# remotoPro1_3.net
KiCad netlist of a schematic drawn in EAGLE
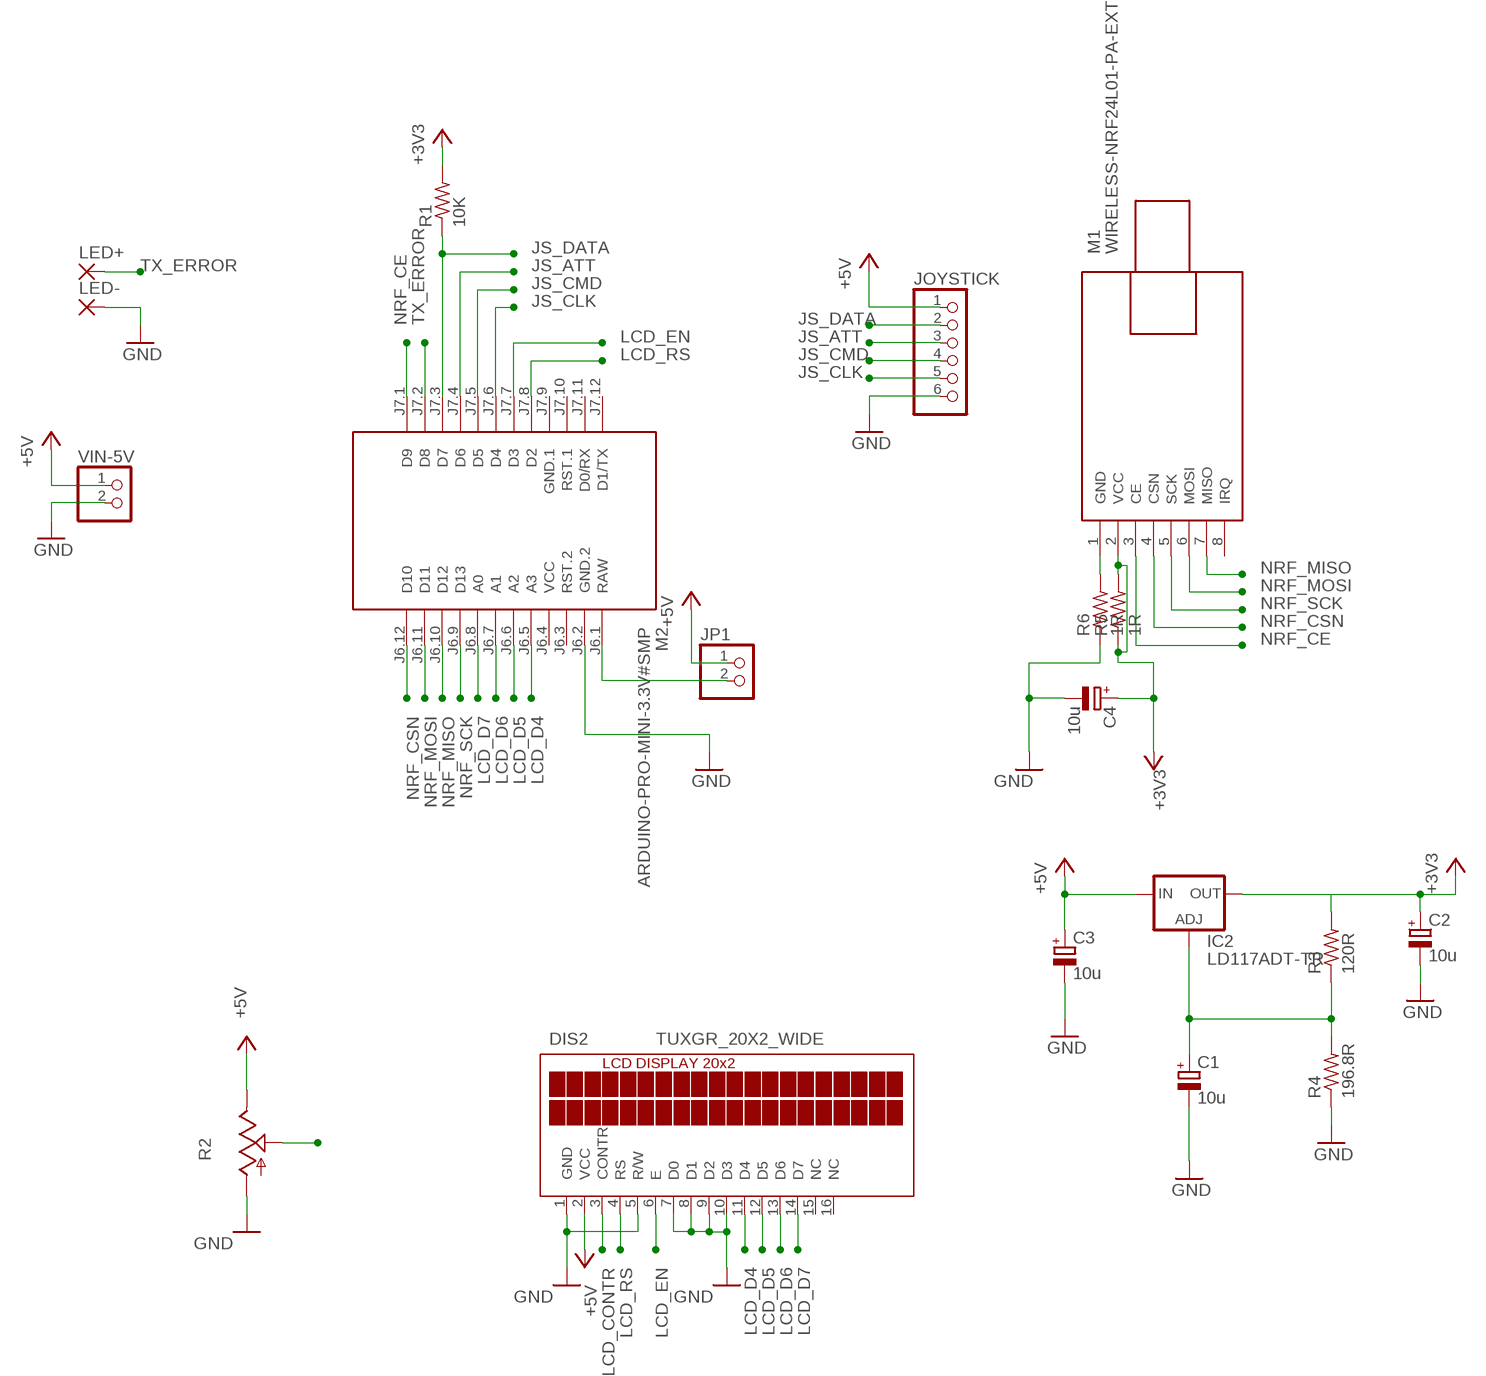
[diagram p0: schematic, sheet 1]

(export (version "E")
  (design (tool "Eeschema 10.0.6"))
  (components
    (comp (ref "C1")
      (value "10u")
      (footprint "eagle-import:E1,8-4")
      (libsource (lib "eagle-import") (part "CPOL-EUE1.8-4"))
    )
    (comp (ref "C2")
      (value "10u")
      (footprint "eagle-import:E1,8-4")
      (libsource (lib "eagle-import") (part "CPOL-EUE1.8-4"))
    )
    (comp (ref "C3")
      (value "10u")
      (footprint "eagle-import:E1,8-4")
      (libsource (lib "eagle-import") (part "CPOL-EUE1.8-4"))
    )
    (comp (ref "C4")
      (value "10u")
      (footprint "eagle-import:E1,8-4")
      (libsource (lib "eagle-import") (part "CPOL-EUE1.8-4"))
    )
    (comp (ref "DIS2")
      (value "TUXGR_20X2_WIDE")
      (footprint "eagle-import:TUXGR_20X2_WIDE")
      (libsource (lib "eagle-import") (part "TUXGR_20X2_WIDE"))
    )
    (comp (ref "IC2")
      (value "LD117ADT-TR")
      (footprint "eagle-import:DPACK")
      (libsource (lib "eagle-import") (part "LD117A?DT-TR"))
    )
    (comp (ref "JOYSTICK")
      (value "PINHD-1X6")
      (footprint "eagle-import:1X06")
      (libsource (lib "eagle-import") (part "PINHD-1X6"))
    )
    (comp (ref "JP1")
      (value "PINHD-1X2")
      (footprint "eagle-import:1X02")
      (libsource (lib "eagle-import") (part "PINHD-1X2"))
    )
    (comp (ref "LED+")
      (value "1,6/0,8")
      (footprint "eagle-import:1,6_0,8")
      (libsource (lib "eagle-import") (part "1,6/0,8"))
    )
    (comp (ref "LED-")
      (value "1,6/0,8")
      (footprint "eagle-import:1,6_0,8")
      (libsource (lib "eagle-import") (part "1,6/0,8"))
    )
    (comp (ref "M1")
      (value "WIRELESS-NRF24L01-PA-EXT")
      (footprint "eagle-import:WIRELESS-NRF24L01-PA-EXT")
      (libsource (lib "eagle-import") (part "WIRELESS-NRF24L01-PA-EXT"))
    )
    (comp (ref "M2")
      (value "ARDUINO-PRO-MINI-3.3V#SMP")
      (footprint "eagle-import:ARDUINO-PRO-MINI#SMP")
      (libsource (lib "eagle-import") (part "ARDUINO-PRO-MINI-#SMP3.3V"))
    )
    (comp (ref "R1")
      (value "10K")
      (footprint "eagle-import:0204_7")
      (libsource (lib "eagle-import") (part "R-US_0204/7"))
    )
    (comp (ref "R2")
      (value "TRIM_US-S75P")
      (footprint "eagle-import:S75P")
      (libsource (lib "eagle-import") (part "TRIM_US-S75P"))
    )
    (comp (ref "R3")
      (value "120R")
      (footprint "eagle-import:0204_7")
      (libsource (lib "eagle-import") (part "R-US_0204/7"))
    )
    (comp (ref "R4")
      (value "196.8R")
      (footprint "eagle-import:0204_7")
      (libsource (lib "eagle-import") (part "R-US_0204/7"))
    )
    (comp (ref "R5")
      (value "1R")
      (footprint "eagle-import:0207_2V")
      (libsource (lib "eagle-import") (part "R-US_0207/2V"))
    )
    (comp (ref "R6")
      (value "1R")
      (footprint "eagle-import:0207_2V")
      (libsource (lib "eagle-import") (part "R-US_0207/2V"))
    )
    (comp (ref "VIN-5V")
      (value "PINHD-1X2")
      (footprint "eagle-import:1X02")
      (libsource (lib "eagle-import") (part "PINHD-1X2"))
    )
  )
  (nets
    (net (code "1") (name "+3V3") (class "Default")
      (node (ref "C2") (pin "+") (pinfunction "+_+") (pintype "passive"))
      (node (ref "C4") (pin "+") (pinfunction "+_+") (pintype "passive"))
      (node (ref "IC2") (pin "4") (pinfunction "OUT_4") (pintype "passive"))
      (node (ref "M1") (pin "2") (pinfunction "VCC_2") (pintype "power_in"))
      (node (ref "R1") (pin "2") (pinfunction "2_2") (pintype "passive"))
      (node (ref "R3") (pin "2") (pinfunction "2_2") (pintype "passive"))
      (node (ref "R5") (pin "1") (pinfunction "1_1") (pintype "passive"))
      (node (ref "R5") (pin "2") (pinfunction "2_2") (pintype "passive"))
    )
    (net (code "2") (name "+5V") (class "Default")
      (node (ref "C3") (pin "+") (pinfunction "+_+") (pintype "passive"))
      (node (ref "DIS2") (pin "2") (pinfunction "VCC_2") (pintype "power_in"))
      (node (ref "IC2") (pin "3") (pinfunction "IN_3") (pintype "input"))
      (node (ref "JOYSTICK") (pin "1") (pinfunction "1_1") (pintype "passive"))
      (node (ref "JP1") (pin "1") (pinfunction "1_1") (pintype "passive"))
      (node (ref "R2") (pin "E") (pinfunction "E_E") (pintype "passive"))
      (node (ref "VIN-5V") (pin "1") (pinfunction "1_1") (pintype "passive"))
    )
    (net (code "3") (name "/GND.1") (class "Default")
      (node (ref "M2") (pin "J7.9") (pinfunction "GND.1_J7.9") (pintype "power_in"))
    )
    (net (code "4") (name "/JS_ATT") (class "Default")
      (node (ref "JOYSTICK") (pin "3") (pinfunction "3_3") (pintype "passive"))
      (node (ref "M2") (pin "J7.4") (pinfunction "D6_J7.4") (pintype "bidirectional"))
    )
    (net (code "5") (name "/JS_CLK") (class "Default")
      (node (ref "JOYSTICK") (pin "5") (pinfunction "5_5") (pintype "passive"))
      (node (ref "M2") (pin "J7.6") (pinfunction "D4_J7.6") (pintype "bidirectional"))
    )
    (net (code "6") (name "/JS_CMD") (class "Default")
      (node (ref "JOYSTICK") (pin "4") (pinfunction "4_4") (pintype "passive"))
      (node (ref "M2") (pin "J7.5") (pinfunction "D5_J7.5") (pintype "bidirectional"))
    )
    (net (code "7") (name "/JS_DATA") (class "Default")
      (node (ref "JOYSTICK") (pin "2") (pinfunction "2_2") (pintype "passive"))
      (node (ref "M2") (pin "J7.3") (pinfunction "D7_J7.3") (pintype "bidirectional"))
      (node (ref "R1") (pin "1") (pinfunction "1_1") (pintype "passive"))
    )
    (net (code "8") (name "/LCD_CONTR") (class "Default")
      (node (ref "DIS2") (pin "3") (pinfunction "CONTR_3") (pintype "input"))
      (node (ref "R2") (pin "S") (pinfunction "S_S") (pintype "passive"))
    )
    (net (code "9") (name "/LCD_D4") (class "Default")
      (node (ref "DIS2") (pin "11") (pinfunction "D4_11") (pintype "input"))
      (node (ref "M2") (pin "J6.5") (pinfunction "A3_J6.5") (pintype "bidirectional"))
    )
    (net (code "10") (name "/LCD_D5") (class "Default")
      (node (ref "DIS2") (pin "12") (pinfunction "D5_12") (pintype "input"))
      (node (ref "M2") (pin "J6.6") (pinfunction "A2_J6.6") (pintype "bidirectional"))
    )
    (net (code "11") (name "/LCD_D6") (class "Default")
      (node (ref "DIS2") (pin "13") (pinfunction "D6_13") (pintype "input"))
      (node (ref "M2") (pin "J6.7") (pinfunction "A1_J6.7") (pintype "bidirectional"))
    )
    (net (code "12") (name "/LCD_D7") (class "Default")
      (node (ref "DIS2") (pin "14") (pinfunction "D7_14") (pintype "input"))
      (node (ref "M2") (pin "J6.8") (pinfunction "A0_J6.8") (pintype "bidirectional"))
    )
    (net (code "13") (name "/LCD_EN") (class "Default")
      (node (ref "DIS2") (pin "6") (pinfunction "E_6") (pintype "input"))
      (node (ref "M2") (pin "J7.7") (pinfunction "D3_J7.7") (pintype "bidirectional"))
    )
    (net (code "14") (name "/LCD_RS") (class "Default")
      (node (ref "DIS2") (pin "4") (pinfunction "RS_4") (pintype "input"))
      (node (ref "M2") (pin "J7.8") (pinfunction "D2_J7.8") (pintype "bidirectional"))
    )
    (net (code "15") (name "/NRF_CE") (class "Default")
      (node (ref "M1") (pin "3") (pinfunction "CE_3") (pintype "bidirectional"))
      (node (ref "M2") (pin "J7.1") (pinfunction "D9_J7.1") (pintype "bidirectional"))
    )
    (net (code "16") (name "/NRF_CSN") (class "Default")
      (node (ref "M1") (pin "4") (pinfunction "CSN_4") (pintype "bidirectional"))
      (node (ref "M2") (pin "J6.12") (pinfunction "D10_J6.12") (pintype "bidirectional"))
    )
    (net (code "17") (name "/NRF_MISO") (class "Default")
      (node (ref "M1") (pin "7") (pinfunction "MISO_7") (pintype "bidirectional"))
      (node (ref "M2") (pin "J6.10") (pinfunction "D12_J6.10") (pintype "bidirectional"))
    )
    (net (code "18") (name "/NRF_MOSI") (class "Default")
      (node (ref "M1") (pin "6") (pinfunction "MOSI_6") (pintype "bidirectional"))
      (node (ref "M2") (pin "J6.11") (pinfunction "D11_J6.11") (pintype "bidirectional"))
    )
    (net (code "19") (name "/NRF_SCK") (class "Default")
      (node (ref "M1") (pin "5") (pinfunction "SCK_5") (pintype "bidirectional"))
      (node (ref "M2") (pin "J6.9") (pinfunction "D13_J6.9") (pintype "bidirectional"))
    )
    (net (code "20") (name "/TX_ERROR") (class "Default")
      (node (ref "LED+") (pin "1") (pinfunction "P_1") (pintype "passive"))
      (node (ref "M2") (pin "J7.2") (pinfunction "D8_J7.2") (pintype "bidirectional"))
    )
    (net (code "21") (name "/VCC") (class "Default")
      (node (ref "M2") (pin "J6.4") (pinfunction "VCC_J6.4") (pintype "power_in"))
    )
    (net (code "22") (name "GND") (class "Default")
      (node (ref "C1") (pin "-") (pinfunction "-_-") (pintype "passive"))
      (node (ref "C2") (pin "-") (pinfunction "-_-") (pintype "passive"))
      (node (ref "C3") (pin "-") (pinfunction "-_-") (pintype "passive"))
      (node (ref "C4") (pin "-") (pinfunction "-_-") (pintype "passive"))
      (node (ref "DIS2") (pin "1") (pinfunction "GND_1") (pintype "power_in"))
      (node (ref "DIS2") (pin "10") (pinfunction "D3_10") (pintype "input"))
      (node (ref "DIS2") (pin "5") (pinfunction "R/W_5") (pintype "input"))
      (node (ref "DIS2") (pin "7") (pinfunction "D0_7") (pintype "input"))
      (node (ref "DIS2") (pin "8") (pinfunction "D1_8") (pintype "input"))
      (node (ref "DIS2") (pin "9") (pinfunction "D2_9") (pintype "input"))
      (node (ref "JOYSTICK") (pin "6") (pinfunction "6_6") (pintype "passive"))
      (node (ref "LED-") (pin "1") (pinfunction "P_1") (pintype "passive"))
      (node (ref "M2") (pin "J6.2") (pinfunction "GND.2_J6.2") (pintype "power_in"))
      (node (ref "R2") (pin "A") (pinfunction "A_A") (pintype "passive"))
      (node (ref "R4") (pin "1") (pinfunction "1_1") (pintype "passive"))
      (node (ref "R6") (pin "1") (pinfunction "1_1") (pintype "passive"))
      (node (ref "VIN-5V") (pin "2") (pinfunction "2_2") (pintype "passive"))
    )
    (net (code "23") (name "Net-(IC2-ADJ)") (class "Default")
      (node (ref "C1") (pin "+") (pinfunction "+_+") (pintype "passive"))
      (node (ref "IC2") (pin "1") (pinfunction "ADJ_1") (pintype "input"))
      (node (ref "R3") (pin "1") (pinfunction "1_1") (pintype "passive"))
      (node (ref "R4") (pin "2") (pinfunction "2_2") (pintype "passive"))
    )
    (net (code "24") (name "Net-(M1-GND)") (class "Default")
      (node (ref "M1") (pin "1") (pinfunction "GND_1") (pintype "power_in"))
      (node (ref "R6") (pin "2") (pinfunction "2_2") (pintype "passive"))
    )
    (net (code "25") (name "Net-(M2-RAW)") (class "Default")
      (node (ref "JP1") (pin "2") (pinfunction "2_2") (pintype "passive"))
      (node (ref "M2") (pin "J6.1") (pinfunction "RAW_J6.1") (pintype "power_in"))
    )
    (net (code "26") (name "unconnected-(DIS2-NC-Pad15)") (class "Default")
      (node (ref "DIS2") (pin "15") (pinfunction "NC_15") (pintype "no_connect"))
    )
    (net (code "27") (name "unconnected-(DIS2-NC-Pad16)") (class "Default")
      (node (ref "DIS2") (pin "16") (pinfunction "NC_16") (pintype "no_connect"))
    )
    (net (code "28") (name "unconnected-(M1-IRQ-Pad8)") (class "Default")
      (node (ref "M1") (pin "8") (pinfunction "IRQ_8") (pintype "bidirectional"))
    )
    (net (code "29") (name "unconnected-(M2-D0{slash}RX-PadJ7.11)") (class "Default")
      (node (ref "M2") (pin "J7.11") (pinfunction "D0/RX_J7.11") (pintype "bidirectional"))
    )
    (net (code "30") (name "unconnected-(M2-D1{slash}TX-PadJ7.12)") (class "Default")
      (node (ref "M2") (pin "J7.12") (pinfunction "D1/TX_J7.12") (pintype "bidirectional"))
    )
    (net (code "31") (name "unconnected-(M2-RST.1-PadJ7.10)") (class "Default")
      (node (ref "M2") (pin "J7.10") (pinfunction "RST.1_J7.10") (pintype "bidirectional"))
    )
    (net (code "32") (name "unconnected-(M2-RST.2-PadJ6.3)") (class "Default")
      (node (ref "M2") (pin "J6.3") (pinfunction "RST.2_J6.3") (pintype "bidirectional"))
    )
  )
)
